# openegg2.net
KiCad netlist of a schematic drawn in EAGLE
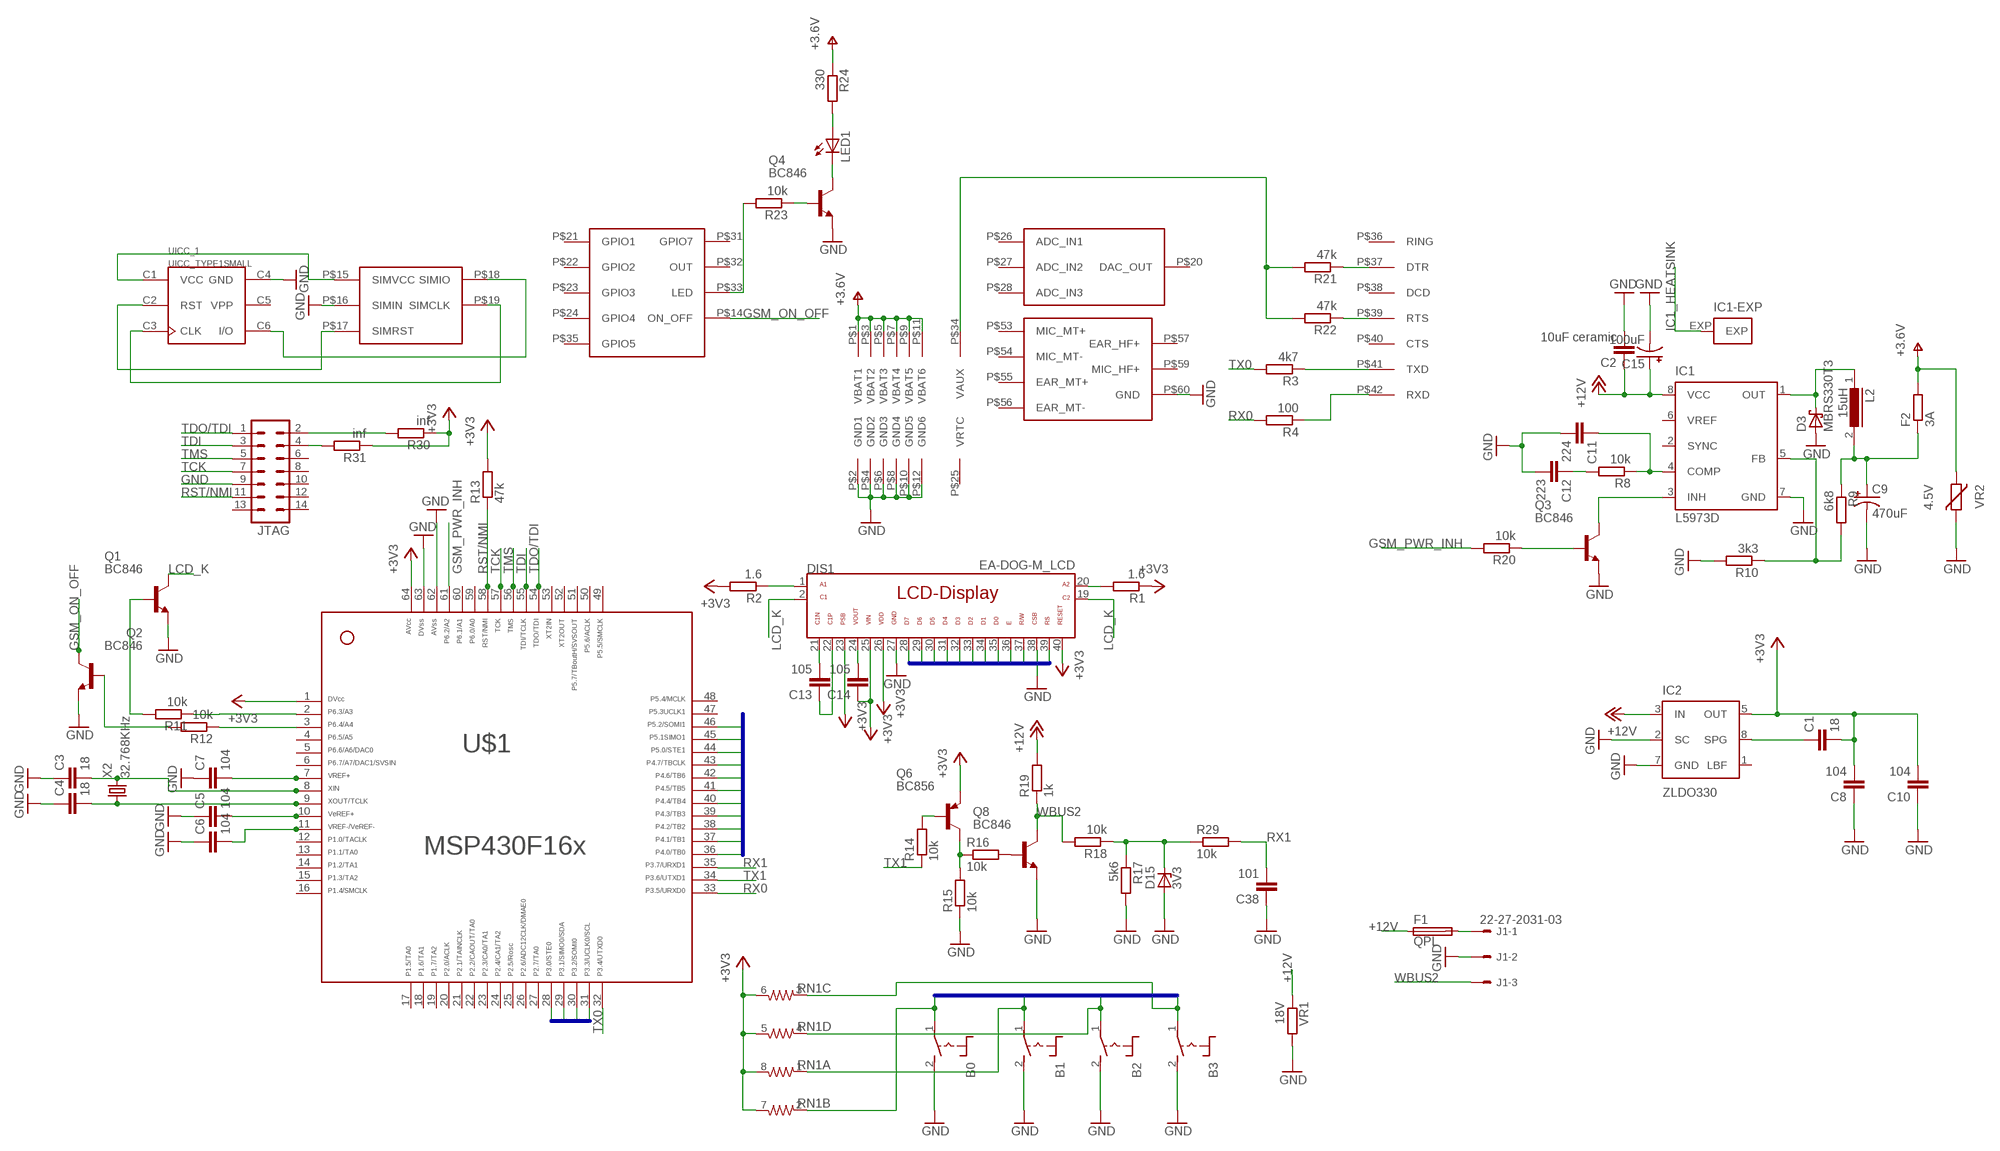
[diagram p0: schematic, sheet 1]

(export (version "E")
  (design (tool "Eeschema 10.0.6"))
  (components
    (comp (ref "B0")
      (value "MARQ6424")
      (footprint "eagle-import:MARQ6424_NOLED")
      (libsource (lib "eagle-import") (part "MARQ6424"))
    )
    (comp (ref "B1")
      (value "MARQ6424")
      (footprint "eagle-import:MARQ6424_NOLED")
      (libsource (lib "eagle-import") (part "MARQ6424"))
    )
    (comp (ref "B2")
      (value "MARQ6424")
      (footprint "eagle-import:MARQ6424_NOLED")
      (libsource (lib "eagle-import") (part "MARQ6424"))
    )
    (comp (ref "B3")
      (value "MARQ6424")
      (footprint "eagle-import:MARQ6424_NOLED")
      (libsource (lib "eagle-import") (part "MARQ6424"))
    )
    (comp (ref "C1")
      (value "18")
      (footprint "eagle-import:C0603")
      (libsource (lib "eagle-import") (part "C-EUC0603"))
    )
    (comp (ref "C2")
      (value "10uF ceramic")
      (footprint "eagle-import:C1210K")
      (libsource (lib "eagle-import") (part "C-EUC1210K"))
    )
    (comp (ref "C3")
      (value "18")
      (footprint "eagle-import:C0603")
      (libsource (lib "eagle-import") (part "C-EUC0603"))
    )
    (comp (ref "C4")
      (value "18")
      (footprint "eagle-import:C0603")
      (libsource (lib "eagle-import") (part "C-EUC0603"))
    )
    (comp (ref "C5")
      (value "104")
      (footprint "eagle-import:C0603")
      (libsource (lib "eagle-import") (part "C-EUC0603"))
    )
    (comp (ref "C6")
      (value "104")
      (footprint "eagle-import:C0603")
      (libsource (lib "eagle-import") (part "C-EUC0603"))
    )
    (comp (ref "C7")
      (value "104")
      (footprint "eagle-import:C0603")
      (libsource (lib "eagle-import") (part "C-EUC0603"))
    )
    (comp (ref "C8")
      (value "104")
      (footprint "eagle-import:C1206")
      (libsource (lib "eagle-import") (part "C-EUC1206"))
    )
    (comp (ref "C9")
      (value "470uF")
      (footprint "eagle-import:CT7343")
      (libsource (lib "eagle-import") (part "CPOL-USCT7343"))
    )
    (comp (ref "C10")
      (value "104")
      (footprint "eagle-import:C1206")
      (libsource (lib "eagle-import") (part "C-EUC1206"))
    )
    (comp (ref "C11")
      (value "224")
      (footprint "eagle-import:C0402")
      (libsource (lib "eagle-import") (part "C-EUC0402"))
    )
    (comp (ref "C12")
      (value "223")
      (footprint "eagle-import:C0402")
      (libsource (lib "eagle-import") (part "C-EUC0402"))
    )
    (comp (ref "C13")
      (value "105")
      (footprint "eagle-import:C1206")
      (libsource (lib "eagle-import") (part "C-EUC1206"))
    )
    (comp (ref "C14")
      (value "105")
      (footprint "eagle-import:C1206")
      (libsource (lib "eagle-import") (part "C-EUC1206"))
    )
    (comp (ref "C15")
      (value "100uF")
      (footprint "eagle-import:153CLV-0505")
      (libsource (lib "eagle-import") (part "CPOL-US153CLV-0505"))
    )
    (comp (ref "C38")
      (value "101")
      (footprint "eagle-import:C0402")
      (libsource (lib "eagle-import") (part "C-EUC0402"))
    )
    (comp (ref "D3")
      (value "MBRS330T3")
      (footprint "eagle-import:SMC")
      (libsource (lib "eagle-import") (part "MBRS30T33"))
    )
    (comp (ref "D15")
      (value "3V3")
      (footprint "eagle-import:SOD80C")
      (libsource (lib "eagle-import") (part "ZENER-DIODESOD80C"))
    )
    (comp (ref "DIS1")
      (value "EA-DOG-M_LCD")
      (footprint "eagle-import:EA-DOG-M_LCD")
      (libsource (lib "eagle-import") (part "EA-DOG-M_LCD"))
    )
    (comp (ref "F1")
      (value "QPL")
      (footprint "eagle-import:QPL")
      (libsource (lib "eagle-import") (part "QPL"))
    )
    (comp (ref "F2")
      (value "3A")
      (footprint "eagle-import:R2010")
      (libsource (lib "eagle-import") (part "R-EU_R2010"))
    )
    (comp (ref "IC1")
      (value "L5973D")
      (footprint "eagle-import:HSOP8")
      (fields (field (name "MF") "STMICROELECTRONICS"))
      (libsource (lib "eagle-import") (part "L5973D"))
    )
    (comp (ref "IC2")
      (value "ZLDO330")
      (footprint "eagle-import:SM8")
      (libsource (lib "eagle-import") (part "ZLDO330"))
    )
    (comp (ref "J1")
      (value "22-27-2031-03")
      (footprint "eagle-import:6410-03")
      (libsource (lib "eagle-import") (part "22-?-0327-2031"))
    )
    (comp (ref "JTAG")
      (value "MA07-2")
      (footprint "eagle-import:MA07-2")
      (libsource (lib "eagle-import") (part "MA07-2"))
    )
    (comp (ref "L2")
      (value "15uH")
      (footprint "eagle-import:DR127")
      (libsource (lib "eagle-import") (part "DR127"))
    )
    (comp (ref "LED1")
      (value "LEDCHIP-LED0603")
      (footprint "eagle-import:CHIP-LED0603")
      (libsource (lib "eagle-import") (part "LEDCHIP-LED0603"))
    )
    (comp (ref "Q1")
      (value "BC846")
      (footprint "eagle-import:SOT23")
      (libsource (lib "eagle-import") (part "BC846SMDALT1"))
    )
    (comp (ref "Q2")
      (value "BC846")
      (footprint "eagle-import:SOT23")
      (libsource (lib "eagle-import") (part "BC846SMDALT1"))
    )
    (comp (ref "Q3")
      (value "BC846")
      (footprint "eagle-import:SOT23")
      (libsource (lib "eagle-import") (part "BC846SMDALT1"))
    )
    (comp (ref "Q4")
      (value "BC846")
      (footprint "eagle-import:SOT23")
      (libsource (lib "eagle-import") (part "BC846SMDALT1"))
    )
    (comp (ref "Q6")
      (value "BC856")
      (footprint "eagle-import:SOT23-BEC")
      (libsource (lib "eagle-import") (part "BC856SMDALT1"))
    )
    (comp (ref "Q8")
      (value "BC846")
      (footprint "eagle-import:SOT23")
      (libsource (lib "eagle-import") (part "BC846SMDALT1"))
    )
    (comp (ref "R1")
      (value "1.6")
      (footprint "eagle-import:R1206")
      (libsource (lib "eagle-import") (part "R-EU_R1206"))
    )
    (comp (ref "R2")
      (value "1.6")
      (footprint "eagle-import:R1206")
      (libsource (lib "eagle-import") (part "R-EU_R1206"))
    )
    (comp (ref "R3")
      (value "4k7")
      (footprint "eagle-import:R0603")
      (libsource (lib "eagle-import") (part "R-EU_R0603"))
    )
    (comp (ref "R4")
      (value "100")
      (footprint "eagle-import:R0603")
      (libsource (lib "eagle-import") (part "R-EU_R0603"))
    )
    (comp (ref "R8")
      (value "10k")
      (footprint "eagle-import:R0603")
      (libsource (lib "eagle-import") (part "R-EU_R0603"))
    )
    (comp (ref "R9")
      (value "6k8")
      (footprint "eagle-import:R0603")
      (libsource (lib "eagle-import") (part "R-EU_R0603"))
    )
    (comp (ref "R10")
      (value "3k3")
      (footprint "eagle-import:R0603")
      (libsource (lib "eagle-import") (part "R-EU_R0603"))
    )
    (comp (ref "R11")
      (value "10k")
      (footprint "eagle-import:R0603")
      (libsource (lib "eagle-import") (part "R-EU_R0603"))
    )
    (comp (ref "R12")
      (value "10k")
      (footprint "eagle-import:R0603")
      (libsource (lib "eagle-import") (part "R-EU_R0603"))
    )
    (comp (ref "R13")
      (value "47k")
      (footprint "eagle-import:R0603")
      (libsource (lib "eagle-import") (part "R-EU_R0603"))
    )
    (comp (ref "R14")
      (value "10k")
      (footprint "eagle-import:R0603")
      (libsource (lib "eagle-import") (part "R-EU_R0603"))
    )
    (comp (ref "R15")
      (value "10k")
      (footprint "eagle-import:R0603")
      (libsource (lib "eagle-import") (part "R-EU_R0603"))
    )
    (comp (ref "R16")
      (value "10k")
      (footprint "eagle-import:R0603")
      (libsource (lib "eagle-import") (part "R-EU_R0603"))
    )
    (comp (ref "R17")
      (value "5k6")
      (footprint "eagle-import:R0603")
      (libsource (lib "eagle-import") (part "R-EU_R0603"))
    )
    (comp (ref "R18")
      (value "10k")
      (footprint "eagle-import:R0603")
      (libsource (lib "eagle-import") (part "R-EU_R0603"))
    )
    (comp (ref "R19")
      (value "1k")
      (footprint "eagle-import:R0603")
      (libsource (lib "eagle-import") (part "R-EU_R0603"))
    )
    (comp (ref "R20")
      (value "10k")
      (footprint "eagle-import:R0603")
      (libsource (lib "eagle-import") (part "R-EU_R0603"))
    )
    (comp (ref "R21")
      (value "47k")
      (footprint "eagle-import:R0603")
      (libsource (lib "eagle-import") (part "R-EU_R0603"))
    )
    (comp (ref "R22")
      (value "47k")
      (footprint "eagle-import:R0603")
      (libsource (lib "eagle-import") (part "R-EU_R0603"))
    )
    (comp (ref "R23")
      (value "10k")
      (footprint "eagle-import:R0603")
      (libsource (lib "eagle-import") (part "R-EU_R0603"))
    )
    (comp (ref "R24")
      (value "330")
      (footprint "eagle-import:R0603")
      (libsource (lib "eagle-import") (part "R-EU_R0603"))
    )
    (comp (ref "R29")
      (value "10k")
      (footprint "eagle-import:R0603")
      (libsource (lib "eagle-import") (part "R-EU_R0603"))
    )
    (comp (ref "R30")
      (value "inf")
      (footprint "eagle-import:R0603")
      (libsource (lib "eagle-import") (part "R-EU_R0603"))
    )
    (comp (ref "R31")
      (value "inf")
      (footprint "eagle-import:R0603")
      (libsource (lib "eagle-import") (part "R-EU_R0603"))
    )
    (comp (ref "RN1")
      (value "742-8_S")
      (footprint "eagle-import:742-8")
      (libsource (lib "eagle-import") (part "742-8_S"))
    )
    (comp (ref "U$1")
      (value "F16X---PM64")
      (footprint "eagle-import:PM_PAG64")
      (libsource (lib "eagle-import") (part "F16X---PM64"))
    )
    (comp (ref "U$2")
      (value "GC864-QUAD-C2SMD")
      (footprint "eagle-import:GC864-QUAD-C2_SMD")
      (libsource (lib "eagle-import") (part "GC864-QUAD-C2SMD"))
    )
    (comp (ref "UICC_1")
      (value "UICC_TYPE1SMALL")
      (footprint "eagle-import:UICC_READER2")
      (libsource (lib "eagle-import") (part "UICC_TYPE1SMALL"))
    )
    (comp (ref "VR1")
      (value "18V")
      (footprint "eagle-import:R2010")
      (libsource (lib "eagle-import") (part "R-EU_R2010"))
    )
    (comp (ref "VR2")
      (value "4.5V")
      (footprint "eagle-import:CT_CN1812")
      (libsource (lib "eagle-import") (part "VARISTORCN1812"))
    )
    (comp (ref "X2")
      (value "32.768KHz")
      (footprint "eagle-import:TC26V")
      (libsource (lib "eagle-import") (part "CRYSTALTC26V"))
    )
  )
  (nets
    (net (code "1") (name "+3.6V") (class "Default")
      (node (ref "F2") (pin "2") (pinfunction "2_2") (pintype "passive"))
      (node (ref "R24") (pin "1") (pinfunction "1_1") (pintype "passive"))
      (node (ref "U$2") (pin "P$1") (pinfunction "VBAT1_P$1") (pintype "power_in"))
      (node (ref "U$2") (pin "P$11") (pinfunction "VBAT6_P$11") (pintype "power_in"))
      (node (ref "U$2") (pin "P$3") (pinfunction "VBAT2_P$3") (pintype "power_in"))
      (node (ref "U$2") (pin "P$5") (pinfunction "VBAT3_P$5") (pintype "power_in"))
      (node (ref "U$2") (pin "P$7") (pinfunction "VBAT4_P$7") (pintype "power_in"))
      (node (ref "U$2") (pin "P$9") (pinfunction "VBAT5_P$9") (pintype "power_in"))
      (node (ref "VR2") (pin "2") (pinfunction "2_2") (pintype "passive"))
    )
    (net (code "2") (name "+3V3") (class "Default")
      (node (ref "C1") (pin "2") (pinfunction "2_2") (pintype "passive"))
      (node (ref "C10") (pin "2") (pinfunction "2_2") (pintype "passive"))
      (node (ref "C14") (pin "1") (pinfunction "1_1") (pintype "passive"))
      (node (ref "C8") (pin "2") (pinfunction "2_2") (pintype "passive"))
      (node (ref "DIS1") (pin "23") (pinfunction "23_23") (pintype "bidirectional"))
      (node (ref "DIS1") (pin "25") (pinfunction "25_25") (pintype "bidirectional"))
      (node (ref "DIS1") (pin "26") (pinfunction "26_26") (pintype "power_in"))
      (node (ref "DIS1") (pin "40") (pinfunction "40_40") (pintype "bidirectional"))
      (node (ref "IC2") (pin "5") (pinfunction "OUT_5") (pintype "power_in"))
      (node (ref "Q6") (pin "E") (pinfunction "E_E") (pintype "passive"))
      (node (ref "R1") (pin "1") (pinfunction "1_1") (pintype "passive"))
      (node (ref "R13") (pin "2") (pinfunction "2_2") (pintype "passive"))
      (node (ref "R2") (pin "2") (pinfunction "2_2") (pintype "passive"))
      (node (ref "R30") (pin "1") (pinfunction "1_1") (pintype "passive"))
      (node (ref "R31") (pin "1") (pinfunction "1_1") (pintype "passive"))
      (node (ref "RN1") (pin "5") (pinfunction "2_5") (pintype "passive"))
      (node (ref "RN1") (pin "6") (pinfunction "2_6") (pintype "passive"))
      (node (ref "RN1") (pin "7") (pinfunction "2_7") (pintype "passive"))
      (node (ref "RN1") (pin "8") (pinfunction "2_8") (pintype "passive"))
      (node (ref "U$1") (pin "1") (pinfunction "1_1") (pintype "power_in"))
      (node (ref "U$1") (pin "64") (pinfunction "64_64") (pintype "power_in"))
    )
    (net (code "3") (name "+12V") (class "Default")
      (node (ref "C15") (pin "+") (pinfunction "+_+") (pintype "passive"))
      (node (ref "C2") (pin "1") (pinfunction "1_1") (pintype "passive"))
      (node (ref "F1") (pin "1") (pinfunction "1_1") (pintype "passive"))
      (node (ref "IC1") (pin "8") (pinfunction "VCC_8") (pintype "input"))
      (node (ref "IC2") (pin "3") (pinfunction "IN_3") (pintype "input"))
      (node (ref "R19") (pin "2") (pinfunction "2_2") (pintype "passive"))
      (node (ref "VR1") (pin "1") (pinfunction "1_1") (pintype "passive"))
    )
    (net (code "4") (name "/B0") (class "Default")
      (node (ref "B0") (pin "1") (pinfunction "P_1") (pintype "passive"))
      (node (ref "RN1") (pin "2") (pinfunction "1_2") (pintype "passive"))
      (node (ref "U$1") (pin "30") (pinfunction "30_30") (pintype "bidirectional"))
    )
    (net (code "5") (name "/B1") (class "Default")
      (node (ref "B1") (pin "1") (pinfunction "P_1") (pintype "passive"))
      (node (ref "RN1") (pin "1") (pinfunction "1_1") (pintype "passive"))
      (node (ref "U$1") (pin "31") (pinfunction "31_31") (pintype "bidirectional"))
    )
    (net (code "6") (name "/B2") (class "Default")
      (node (ref "B2") (pin "1") (pinfunction "P_1") (pintype "passive"))
      (node (ref "RN1") (pin "4") (pinfunction "1_4") (pintype "passive"))
      (node (ref "U$1") (pin "28") (pinfunction "28_28") (pintype "bidirectional"))
    )
    (net (code "7") (name "/B3") (class "Default")
      (node (ref "B3") (pin "1") (pinfunction "P_1") (pintype "passive"))
      (node (ref "RN1") (pin "3") (pinfunction "1_3") (pintype "passive"))
      (node (ref "U$1") (pin "29") (pinfunction "29_29") (pintype "bidirectional"))
    )
    (net (code "8") (name "/D0") (class "Default")
      (node (ref "DIS1") (pin "35") (pinfunction "35_35") (pintype "bidirectional"))
      (node (ref "U$1") (pin "36") (pinfunction "36_36") (pintype "output"))
    )
    (net (code "9") (name "/D1") (class "Default")
      (node (ref "DIS1") (pin "34") (pinfunction "34_34") (pintype "bidirectional"))
      (node (ref "U$1") (pin "37") (pinfunction "37_37") (pintype "bidirectional"))
    )
    (net (code "10") (name "/D2") (class "Default")
      (node (ref "DIS1") (pin "33") (pinfunction "33_33") (pintype "bidirectional"))
      (node (ref "U$1") (pin "38") (pinfunction "38_38") (pintype "bidirectional"))
    )
    (net (code "11") (name "/D3") (class "Default")
      (node (ref "DIS1") (pin "32") (pinfunction "32_32") (pintype "bidirectional"))
      (node (ref "U$1") (pin "39") (pinfunction "39_39") (pintype "bidirectional"))
    )
    (net (code "12") (name "/D4") (class "Default")
      (node (ref "DIS1") (pin "31") (pinfunction "31_31") (pintype "bidirectional"))
      (node (ref "U$1") (pin "40") (pinfunction "40_40") (pintype "input"))
    )
    (net (code "13") (name "/D5") (class "Default")
      (node (ref "DIS1") (pin "30") (pinfunction "30_30") (pintype "bidirectional"))
      (node (ref "U$1") (pin "41") (pinfunction "41_41") (pintype "bidirectional"))
    )
    (net (code "14") (name "/D6") (class "Default")
      (node (ref "DIS1") (pin "29") (pinfunction "29_29") (pintype "bidirectional"))
      (node (ref "U$1") (pin "42") (pinfunction "42_42") (pintype "bidirectional"))
    )
    (net (code "15") (name "/D7") (class "Default")
      (node (ref "DIS1") (pin "28") (pinfunction "28_28") (pintype "bidirectional"))
      (node (ref "U$1") (pin "43") (pinfunction "43_43") (pintype "bidirectional"))
    )
    (net (code "16") (name "/E") (class "Default")
      (node (ref "DIS1") (pin "36") (pinfunction "36_36") (pintype "bidirectional"))
      (node (ref "U$1") (pin "45") (pinfunction "45_45") (pintype "bidirectional"))
    )
    (net (code "17") (name "/GSM_ON_OFF") (class "Default")
      (node (ref "Q2") (pin "3") (pinfunction "C_3") (pintype "passive"))
      (node (ref "U$2") (pin "P$14") (pinfunction "ON_OFF_P$14") (pintype "input"))
    )
    (net (code "18") (name "/GSM_PWR_INH") (class "Default")
      (node (ref "R20") (pin "2") (pinfunction "2_2") (pintype "passive"))
      (node (ref "U$1") (pin "61") (pinfunction "61_61") (pintype "bidirectional"))
    )
    (net (code "19") (name "/IC1_HEATSINK") (class "Default")
      (node (ref "IC1") (pin "EXP") (pinfunction "EXP_EXP") (pintype "input"))
    )
    (net (code "20") (name "/LCD_K") (class "Default")
      (node (ref "DIS1") (pin "19") (pinfunction "19_19") (pintype "passive"))
      (node (ref "DIS1") (pin "2") (pinfunction "2_2") (pintype "passive"))
      (node (ref "Q1") (pin "3") (pinfunction "C_3") (pintype "passive"))
    )
    (net (code "21") (name "/RS") (class "Default")
      (node (ref "DIS1") (pin "39") (pinfunction "39_39") (pintype "bidirectional"))
      (node (ref "U$1") (pin "46") (pinfunction "46_46") (pintype "bidirectional"))
    )
    (net (code "22") (name "/RST{slash}NMI") (class "Default")
      (node (ref "JTAG") (pin "11") (pinfunction "11_11") (pintype "passive"))
      (node (ref "R13") (pin "1") (pinfunction "1_1") (pintype "passive"))
      (node (ref "U$1") (pin "58") (pinfunction "58_58") (pintype "input"))
    )
    (net (code "23") (name "/RW") (class "Default")
      (node (ref "DIS1") (pin "37") (pinfunction "37_37") (pintype "bidirectional"))
      (node (ref "U$1") (pin "44") (pinfunction "44_44") (pintype "bidirectional"))
    )
    (net (code "24") (name "/RX0") (class "Default")
      (node (ref "R4") (pin "2") (pinfunction "2_2") (pintype "passive"))
      (node (ref "U$1") (pin "33") (pinfunction "33_33") (pintype "bidirectional"))
    )
    (net (code "25") (name "/RX1") (class "Default")
      (node (ref "C38") (pin "2") (pinfunction "2_2") (pintype "passive"))
      (node (ref "R29") (pin "2") (pinfunction "2_2") (pintype "passive"))
      (node (ref "U$1") (pin "35") (pinfunction "35_35") (pintype "bidirectional"))
    )
    (net (code "26") (name "/TCK") (class "Default")
      (node (ref "JTAG") (pin "7") (pinfunction "7_7") (pintype "passive"))
      (node (ref "U$1") (pin "57") (pinfunction "57_57") (pintype "input"))
    )
    (net (code "27") (name "/TDI") (class "Default")
      (node (ref "JTAG") (pin "3") (pinfunction "3_3") (pintype "passive"))
      (node (ref "U$1") (pin "55") (pinfunction "55_55") (pintype "input"))
    )
    (net (code "28") (name "/TDO{slash}TDI") (class "Default")
      (node (ref "JTAG") (pin "1") (pinfunction "1_1") (pintype "passive"))
      (node (ref "U$1") (pin "54") (pinfunction "54_54") (pintype "bidirectional"))
    )
    (net (code "29") (name "/TMS") (class "Default")
      (node (ref "JTAG") (pin "5") (pinfunction "5_5") (pintype "passive"))
      (node (ref "U$1") (pin "56") (pinfunction "56_56") (pintype "input"))
    )
    (net (code "30") (name "/TX0") (class "Default")
      (node (ref "R3") (pin "2") (pinfunction "2_2") (pintype "passive"))
      (node (ref "U$1") (pin "32") (pinfunction "32_32") (pintype "bidirectional"))
    )
    (net (code "31") (name "/TX1") (class "Default")
      (node (ref "R14") (pin "1") (pinfunction "1_1") (pintype "passive"))
      (node (ref "U$1") (pin "34") (pinfunction "34_34") (pintype "bidirectional"))
    )
    (net (code "32") (name "/VPP") (class "Default")
      (node (ref "UICC_1") (pin "C5") (pinfunction "VPP_C5") (pintype "power_in"))
    )
    (net (code "33") (name "/WBUS2") (class "Default")
      (node (ref "J1") (pin "3") (pinfunction "S_3") (pintype "passive"))
      (node (ref "Q8") (pin "3") (pinfunction "C_3") (pintype "passive"))
      (node (ref "R18") (pin "2") (pinfunction "2_2") (pintype "passive"))
      (node (ref "R19") (pin "1") (pinfunction "1_1") (pintype "passive"))
    )
    (net (code "34") (name "GND") (class "Default")
      (node (ref "B0") (pin "2") (pinfunction "S_2") (pintype "passive"))
      (node (ref "B1") (pin "2") (pinfunction "S_2") (pintype "passive"))
      (node (ref "B2") (pin "2") (pinfunction "S_2") (pintype "passive"))
      (node (ref "B3") (pin "2") (pinfunction "S_2") (pintype "passive"))
      (node (ref "C10") (pin "1") (pinfunction "1_1") (pintype "passive"))
      (node (ref "C11") (pin "2") (pinfunction "2_2") (pintype "passive"))
      (node (ref "C12") (pin "2") (pinfunction "2_2") (pintype "passive"))
      (node (ref "C15") (pin "-") (pinfunction "-_-") (pintype "passive"))
      (node (ref "C2") (pin "2") (pinfunction "2_2") (pintype "passive"))
      (node (ref "C3") (pin "1") (pinfunction "1_1") (pintype "passive"))
      (node (ref "C38") (pin "1") (pinfunction "1_1") (pintype "passive"))
      (node (ref "C4") (pin "1") (pinfunction "1_1") (pintype "passive"))
      (node (ref "C5") (pin "1") (pinfunction "1_1") (pintype "passive"))
      (node (ref "C6") (pin "1") (pinfunction "1_1") (pintype "passive"))
      (node (ref "C7") (pin "1") (pinfunction "1_1") (pintype "passive"))
      (node (ref "C8") (pin "1") (pinfunction "1_1") (pintype "passive"))
      (node (ref "C9") (pin "-") (pinfunction "-_-") (pintype "passive"))
      (node (ref "D15") (pin "A") (pinfunction "A_A") (pintype "passive"))
      (node (ref "D3") (pin "A") (pinfunction "A_A") (pintype "passive"))
      (node (ref "DIS1") (pin "27") (pinfunction "27_27") (pintype "power_in"))
      (node (ref "DIS1") (pin "38") (pinfunction "38_38") (pintype "bidirectional"))
      (node (ref "IC1") (pin "7") (pinfunction "GND_7") (pintype "power_in"))
      (node (ref "IC2") (pin "2") (pinfunction "SC_2") (pintype "input"))
      (node (ref "IC2") (pin "7") (pinfunction "GND_7") (pintype "power_in"))
      (node (ref "J1") (pin "2") (pinfunction "S_2") (pintype "passive"))
      (node (ref "JTAG") (pin "9") (pinfunction "9_9") (pintype "passive"))
      (node (ref "Q1") (pin "2") (pinfunction "E_2") (pintype "passive"))
      (node (ref "Q2") (pin "2") (pinfunction "E_2") (pintype "passive"))
      (node (ref "Q3") (pin "2") (pinfunction "E_2") (pintype "passive"))
      (node (ref "Q4") (pin "2") (pinfunction "E_2") (pintype "passive"))
      (node (ref "Q8") (pin "2") (pinfunction "E_2") (pintype "passive"))
      (node (ref "R10") (pin "2") (pinfunction "2_2") (pintype "passive"))
      (node (ref "R15") (pin "1") (pinfunction "1_1") (pintype "passive"))
      (node (ref "R17") (pin "2") (pinfunction "2_2") (pintype "passive"))
      (node (ref "U$1") (pin "62") (pinfunction "62_62") (pintype "power_in"))
      (node (ref "U$1") (pin "63") (pinfunction "63_63") (pintype "power_in"))
      (node (ref "U$2") (pin "P$10") (pinfunction "GND5_P$10") (pintype "power_in"))
      (node (ref "U$2") (pin "P$12") (pinfunction "GND6_P$12") (pintype "power_in"))
      (node (ref "U$2") (pin "P$16") (pinfunction "SIMIN_P$16") (pintype "input"))
      (node (ref "U$2") (pin "P$2") (pinfunction "GND1_P$2") (pintype "power_in"))
      (node (ref "U$2") (pin "P$4") (pinfunction "GND2_P$4") (pintype "power_in"))
      (node (ref "U$2") (pin "P$6") (pinfunction "GND3_P$6") (pintype "power_in"))
      (node (ref "U$2") (pin "P$60") (pinfunction "GND_P$60") (pintype "power_in"))
      (node (ref "U$2") (pin "P$8") (pinfunction "GND4_P$8") (pintype "power_in"))
      (node (ref "UICC_1") (pin "C4") (pinfunction "GND_C4") (pintype "power_in"))
      (node (ref "VR1") (pin "2") (pinfunction "2_2") (pintype "passive"))
      (node (ref "VR2") (pin "1") (pinfunction "1_1") (pintype "passive"))
    )
    (net (code "35") (name "Net-(C3-Pad2)") (class "Default")
      (node (ref "C3") (pin "2") (pinfunction "2_2") (pintype "passive"))
      (node (ref "U$1") (pin "8") (pinfunction "8_8") (pintype "input"))
      (node (ref "X2") (pin "2") (pinfunction "2_2") (pintype "passive"))
    )
    (net (code "36") (name "Net-(C4-Pad2)") (class "Default")
      (node (ref "C4") (pin "2") (pinfunction "2_2") (pintype "passive"))
      (node (ref "U$1") (pin "9") (pinfunction "9_9") (pintype "bidirectional"))
      (node (ref "X2") (pin "1") (pinfunction "1_1") (pintype "passive"))
    )
    (net (code "37") (name "Net-(C5-Pad2)") (class "Default")
      (node (ref "C5") (pin "2") (pinfunction "2_2") (pintype "passive"))
      (node (ref "U$1") (pin "10") (pinfunction "10_10") (pintype "input"))
    )
    (net (code "38") (name "Net-(C6-Pad2)") (class "Default")
      (node (ref "C6") (pin "2") (pinfunction "2_2") (pintype "passive"))
      (node (ref "U$1") (pin "11") (pinfunction "11_11") (pintype "bidirectional"))
    )
    (net (code "39") (name "Net-(C7-Pad2)") (class "Default")
      (node (ref "C7") (pin "2") (pinfunction "2_2") (pintype "passive"))
      (node (ref "U$1") (pin "7") (pinfunction "7_7") (pintype "output"))
    )
    (net (code "40") (name "Net-(C9-Pad+)") (class "Default")
      (node (ref "C9") (pin "+") (pinfunction "+_+") (pintype "passive"))
      (node (ref "F2") (pin "1") (pinfunction "1_1") (pintype "passive"))
      (node (ref "L2") (pin "2") (pinfunction "2_2") (pintype "passive"))
      (node (ref "R9") (pin "1") (pinfunction "1_1") (pintype "passive"))
    )
    (net (code "41") (name "Net-(C12-Pad1)") (class "Default")
      (node (ref "C12") (pin "1") (pinfunction "1_1") (pintype "passive"))
      (node (ref "R8") (pin "2") (pinfunction "2_2") (pintype "passive"))
    )
    (net (code "42") (name "Net-(C13-Pad1)") (class "Default")
      (node (ref "C13") (pin "1") (pinfunction "1_1") (pintype "passive"))
      (node (ref "DIS1") (pin "22") (pinfunction "22_22") (pintype "bidirectional"))
    )
    (net (code "43") (name "Net-(C13-Pad2)") (class "Default")
      (node (ref "C13") (pin "2") (pinfunction "2_2") (pintype "passive"))
      (node (ref "DIS1") (pin "21") (pinfunction "21_21") (pintype "bidirectional"))
    )
    (net (code "44") (name "Net-(C14-Pad2)") (class "Default")
      (node (ref "C14") (pin "2") (pinfunction "2_2") (pintype "passive"))
      (node (ref "DIS1") (pin "24") (pinfunction "24_24") (pintype "bidirectional"))
    )
    (net (code "45") (name "Net-(D15-PadC)") (class "Default")
      (node (ref "D15") (pin "C") (pinfunction "C_C") (pintype "passive"))
      (node (ref "R17") (pin "1") (pinfunction "1_1") (pintype "passive"))
      (node (ref "R18") (pin "1") (pinfunction "1_1") (pintype "passive"))
      (node (ref "R29") (pin "1") (pinfunction "1_1") (pintype "passive"))
    )
    (net (code "46") (name "Net-(DIS1-Pad1)") (class "Default")
      (node (ref "DIS1") (pin "1") (pinfunction "1_1") (pintype "passive"))
      (node (ref "R2") (pin "1") (pinfunction "1_1") (pintype "passive"))
    )
    (net (code "47") (name "Net-(DIS1-Pad20)") (class "Default")
      (node (ref "DIS1") (pin "20") (pinfunction "20_20") (pintype "passive"))
      (node (ref "R1") (pin "2") (pinfunction "2_2") (pintype "passive"))
    )
    (net (code "48") (name "Net-(IC1B-COMP)") (class "Default")
      (node (ref "C11") (pin "1") (pinfunction "1_1") (pintype "passive"))
      (node (ref "IC1") (pin "4") (pinfunction "COMP_4") (pintype "passive"))
      (node (ref "R8") (pin "1") (pinfunction "1_1") (pintype "passive"))
    )
    (net (code "49") (name "Net-(IC1B-FB)") (class "Default")
      (node (ref "IC1") (pin "5") (pinfunction "FB_5") (pintype "input"))
      (node (ref "R10") (pin "1") (pinfunction "1_1") (pintype "passive"))
      (node (ref "R9") (pin "2") (pinfunction "2_2") (pintype "passive"))
    )
    (net (code "50") (name "Net-(IC1B-INH)") (class "Default")
      (node (ref "IC1") (pin "3") (pinfunction "INH_3") (pintype "input"))
      (node (ref "Q3") (pin "3") (pinfunction "C_3") (pintype "passive"))
    )
    (net (code "51") (name "Net-(IC1B-OUT)") (class "Default")
      (node (ref "D3") (pin "C") (pinfunction "C_C") (pintype "passive"))
      (node (ref "IC1") (pin "1") (pinfunction "OUT_1") (pintype "output"))
      (node (ref "L2") (pin "1") (pinfunction "1_1") (pintype "passive"))
    )
    (net (code "52") (name "Net-(IC2-SPG)") (class "Default")
      (node (ref "C1") (pin "1") (pinfunction "1_1") (pintype "passive"))
      (node (ref "IC2") (pin "8") (pinfunction "SPG_8") (pintype "input"))
    )
    (net (code "53") (name "Net-(J1A-S)") (class "Default")
      (node (ref "F1") (pin "2") (pinfunction "2_2") (pintype "passive"))
      (node (ref "J1") (pin "1") (pinfunction "S_1") (pintype "passive"))
    )
    (net (code "54") (name "Net-(JTAG-Pad2)") (class "Default")
      (node (ref "JTAG") (pin "2") (pinfunction "2_2") (pintype "passive"))
      (node (ref "R30") (pin "2") (pinfunction "2_2") (pintype "passive"))
    )
    (net (code "55") (name "Net-(JTAG-Pad4)") (class "Default")
      (node (ref "JTAG") (pin "4") (pinfunction "4_4") (pintype "passive"))
      (node (ref "R31") (pin "2") (pinfunction "2_2") (pintype "passive"))
    )
    (net (code "56") (name "Net-(LED1-PadA)") (class "Default")
      (node (ref "LED1") (pin "A") (pinfunction "A_A") (pintype "passive"))
      (node (ref "R24") (pin "2") (pinfunction "2_2") (pintype "passive"))
    )
    (net (code "57") (name "Net-(Q1-B)") (class "Default")
      (node (ref "Q1") (pin "1") (pinfunction "B_1") (pintype "passive"))
      (node (ref "R11") (pin "2") (pinfunction "2_2") (pintype "passive"))
    )
    (net (code "58") (name "Net-(Q2-B)") (class "Default")
      (node (ref "Q2") (pin "1") (pinfunction "B_1") (pintype "passive"))
      (node (ref "R12") (pin "2") (pinfunction "2_2") (pintype "passive"))
    )
    (net (code "59") (name "Net-(Q3-B)") (class "Default")
      (node (ref "Q3") (pin "1") (pinfunction "B_1") (pintype "passive"))
      (node (ref "R20") (pin "1") (pinfunction "1_1") (pintype "passive"))
    )
    (net (code "60") (name "Net-(Q4-B)") (class "Default")
      (node (ref "Q4") (pin "1") (pinfunction "B_1") (pintype "passive"))
      (node (ref "R23") (pin "1") (pinfunction "1_1") (pintype "passive"))
    )
    (net (code "61") (name "Net-(Q4-C)") (class "Default")
      (node (ref "LED1") (pin "C") (pinfunction "C_C") (pintype "passive"))
      (node (ref "Q4") (pin "3") (pinfunction "C_3") (pintype "passive"))
    )
    (net (code "62") (name "Net-(Q6-PadB)") (class "Default")
      (node (ref "Q6") (pin "B") (pinfunction "B_B") (pintype "passive"))
      (node (ref "R14") (pin "2") (pinfunction "2_2") (pintype "passive"))
    )
    (net (code "63") (name "Net-(Q6-PadC)") (class "Default")
      (node (ref "Q6") (pin "C") (pinfunction "C_C") (pintype "passive"))
      (node (ref "R15") (pin "2") (pinfunction "2_2") (pintype "passive"))
      (node (ref "R16") (pin "1") (pinfunction "1_1") (pintype "passive"))
    )
    (net (code "64") (name "Net-(Q8-B)") (class "Default")
      (node (ref "Q8") (pin "1") (pinfunction "B_1") (pintype "passive"))
      (node (ref "R16") (pin "2") (pinfunction "2_2") (pintype "passive"))
    )
    (net (code "65") (name "Net-(R11-Pad1)") (class "Default")
      (node (ref "R11") (pin "1") (pinfunction "1_1") (pintype "passive"))
      (node (ref "U$1") (pin "2") (pinfunction "2_2") (pintype "bidirectional"))
    )
    (net (code "66") (name "Net-(R12-Pad1)") (class "Default")
      (node (ref "R12") (pin "1") (pinfunction "1_1") (pintype "passive"))
      (node (ref "U$1") (pin "3") (pinfunction "3_3") (pintype "bidirectional"))
    )
    (net (code "67") (name "Net-(U$2A-VAUX)") (class "Default")
      (node (ref "R21") (pin "2") (pinfunction "2_2") (pintype "passive"))
      (node (ref "R22") (pin "2") (pinfunction "2_2") (pintype "passive"))
      (node (ref "U$2") (pin "P$34") (pinfunction "VAUX_P$34") (pintype "power_in"))
    )
    (net (code "68") (name "Net-(U$2D-LED)") (class "Default")
      (node (ref "R23") (pin "2") (pinfunction "2_2") (pintype "passive"))
      (node (ref "U$2") (pin "P$33") (pinfunction "LED_P$33") (pintype "output"))
    )
    (net (code "69") (name "Net-(U$2E-SIMCLK)") (class "Default")
      (node (ref "U$2") (pin "P$19") (pinfunction "SIMCLK_P$19") (pintype "output"))
      (node (ref "UICC_1") (pin "C3") (pinfunction "CLK_C3") (pintype "input"))
    )
    (net (code "70") (name "Net-(U$2E-SIMIO)") (class "Default")
      (node (ref "U$2") (pin "P$18") (pinfunction "SIMIO_P$18") (pintype "bidirectional"))
      (node (ref "UICC_1") (pin "C6") (pinfunction "I/O_C6") (pintype "bidirectional"))
    )
    (net (code "71") (name "Net-(U$2E-SIMRST)") (class "Default")
      (node (ref "U$2") (pin "P$17") (pinfunction "SIMRST_P$17") (pintype "output"))
      (node (ref "UICC_1") (pin "C2") (pinfunction "RST_C2") (pintype "input"))
    )
    (net (code "72") (name "Net-(U$2E-SIMVCC)") (class "Default")
      (node (ref "U$2") (pin "P$15") (pinfunction "SIMVCC_P$15") (pintype "power_in"))
      (node (ref "UICC_1") (pin "C1") (pinfunction "VCC_C1") (pintype "power_in"))
    )
    (net (code "73") (name "Net-(U$2F-DTR)") (class "Default")
      (node (ref "R21") (pin "1") (pinfunction "1_1") (pintype "passive"))
      (node (ref "U$2") (pin "P$37") (pinfunction "DTR_P$37") (pintype "input"))
    )
    (net (code "74") (name "Net-(U$2F-RTS)") (class "Default")
      (node (ref "R22") (pin "1") (pinfunction "1_1") (pintype "passive"))
      (node (ref "U$2") (pin "P$39") (pinfunction "RTS_P$39") (pintype "input"))
    )
    (net (code "75") (name "Net-(U$2F-RXD)") (class "Default")
      (node (ref "R4") (pin "1") (pinfunction "1_1") (pintype "passive"))
      (node (ref "U$2") (pin "P$42") (pinfunction "RXD_P$42") (pintype "output"))
    )
    (net (code "76") (name "Net-(U$2F-TXD)") (class "Default")
      (node (ref "R3") (pin "1") (pinfunction "1_1") (pintype "passive"))
      (node (ref "U$2") (pin "P$41") (pinfunction "TXD_P$41") (pintype "input"))
    )
    (net (code "77") (name "unconnected-(IC1B-SYNC-Pad2)") (class "Default")
      (node (ref "IC1") (pin "2") (pinfunction "SYNC_2") (pintype "input"))
    )
    (net (code "78") (name "unconnected-(IC1B-VREF-Pad6)") (class "Default")
      (node (ref "IC1") (pin "6") (pinfunction "VREF_6") (pintype "input"))
    )
    (net (code "79") (name "unconnected-(IC2-LBF-Pad1)") (class "Default")
      (node (ref "IC2") (pin "1") (pinfunction "LBF_1") (pintype "output"))
    )
    (net (code "80") (name "unconnected-(JTAG-Pad6)") (class "Default")
      (node (ref "JTAG") (pin "6") (pinfunction "6_6") (pintype "passive"))
    )
    (net (code "81") (name "unconnected-(JTAG-Pad8)") (class "Default")
      (node (ref "JTAG") (pin "8") (pinfunction "8_8") (pintype "passive"))
    )
    (net (code "82") (name "unconnected-(JTAG-Pad10)") (class "Default")
      (node (ref "JTAG") (pin "10") (pinfunction "10_10") (pintype "passive"))
    )
    (net (code "83") (name "unconnected-(JTAG-Pad12)") (class "Default")
      (node (ref "JTAG") (pin "12") (pinfunction "12_12") (pintype "passive"))
    )
    (net (code "84") (name "unconnected-(JTAG-Pad13)") (class "Default")
      (node (ref "JTAG") (pin "13") (pinfunction "13_13") (pintype "passive"))
    )
    (net (code "85") (name "unconnected-(JTAG-Pad14)") (class "Default")
      (node (ref "JTAG") (pin "14") (pinfunction "14_14") (pintype "passive"))
    )
    (net (code "86") (name "unconnected-(U$1-Pad4)") (class "Default")
      (node (ref "U$1") (pin "4") (pinfunction "4_4") (pintype "bidirectional"))
    )
    (net (code "87") (name "unconnected-(U$1-Pad5)") (class "Default")
      (node (ref "U$1") (pin "5") (pinfunction "5_5") (pintype "bidirectional"))
    )
    (net (code "88") (name "unconnected-(U$1-Pad6)") (class "Default")
      (node (ref "U$1") (pin "6") (pinfunction "6_6") (pintype "bidirectional"))
    )
    (net (code "89") (name "unconnected-(U$1-Pad12)") (class "Default")
      (node (ref "U$1") (pin "12") (pinfunction "12_12") (pintype "bidirectional"))
    )
    (net (code "90") (name "unconnected-(U$1-Pad13)") (class "Default")
      (node (ref "U$1") (pin "13") (pinfunction "13_13") (pintype "bidirectional"))
    )
    (net (code "91") (name "unconnected-(U$1-Pad14)") (class "Default")
      (node (ref "U$1") (pin "14") (pinfunction "14_14") (pintype "bidirectional"))
    )
    (net (code "92") (name "unconnected-(U$1-Pad15)") (class "Default")
      (node (ref "U$1") (pin "15") (pinfunction "15_15") (pintype "bidirectional"))
    )
    (net (code "93") (name "unconnected-(U$1-Pad16)") (class "Default")
      (node (ref "U$1") (pin "16") (pinfunction "16_16") (pintype "bidirectional"))
    )
    (net (code "94") (name "unconnected-(U$1-Pad17)") (class "Default")
      (node (ref "U$1") (pin "17") (pinfunction "17_17") (pintype "bidirectional"))
    )
    (net (code "95") (name "unconnected-(U$1-Pad18)") (class "Default")
      (node (ref "U$1") (pin "18") (pinfunction "18_18") (pintype "bidirectional"))
    )
    (net (code "96") (name "unconnected-(U$1-Pad19)") (class "Default")
      (node (ref "U$1") (pin "19") (pinfunction "19_19") (pintype "bidirectional"))
    )
    (net (code "97") (name "unconnected-(U$1-Pad20)") (class "Default")
      (node (ref "U$1") (pin "20") (pinfunction "20_20") (pintype "bidirectional"))
    )
    (net (code "98") (name "unconnected-(U$1-Pad21)") (class "Default")
      (node (ref "U$1") (pin "21") (pinfunction "21_21") (pintype "bidirectional"))
    )
    (net (code "99") (name "unconnected-(U$1-Pad22)") (class "Default")
      (node (ref "U$1") (pin "22") (pinfunction "22_22") (pintype "bidirectional"))
    )
    (net (code "100") (name "unconnected-(U$1-Pad23)") (class "Default")
      (node (ref "U$1") (pin "23") (pinfunction "23_23") (pintype "bidirectional"))
    )
    (net (code "101") (name "unconnected-(U$1-Pad24)") (class "Default")
      (node (ref "U$1") (pin "24") (pinfunction "24_24") (pintype "bidirectional"))
    )
    (net (code "102") (name "unconnected-(U$1-Pad25)") (class "Default")
      (node (ref "U$1") (pin "25") (pinfunction "25_25") (pintype "bidirectional"))
    )
    (net (code "103") (name "unconnected-(U$1-Pad26)") (class "Default")
      (node (ref "U$1") (pin "26") (pinfunction "26_26") (pintype "bidirectional"))
    )
    (net (code "104") (name "unconnected-(U$1-Pad27)") (class "Default")
      (node (ref "U$1") (pin "27") (pinfunction "27_27") (pintype "bidirectional"))
    )
    (net (code "105") (name "unconnected-(U$1-Pad47)") (class "Default")
      (node (ref "U$1") (pin "47") (pinfunction "47_47") (pintype "bidirectional"))
    )
    (net (code "106") (name "unconnected-(U$1-Pad48)") (class "Default")
      (node (ref "U$1") (pin "48") (pinfunction "48_48") (pintype "bidirectional"))
    )
    (net (code "107") (name "unconnected-(U$1-Pad49)") (class "Default")
      (node (ref "U$1") (pin "49") (pinfunction "49_49") (pintype "bidirectional"))
    )
    (net (code "108") (name "unconnected-(U$1-Pad50)") (class "Default")
      (node (ref "U$1") (pin "50") (pinfunction "50_50") (pintype "bidirectional"))
    )
    (net (code "109") (name "unconnected-(U$1-Pad51)") (class "Default")
      (node (ref "U$1") (pin "51") (pinfunction "51_51") (pintype "bidirectional"))
    )
    (net (code "110") (name "unconnected-(U$1-Pad52)") (class "Default")
      (node (ref "U$1") (pin "52") (pinfunction "52_52") (pintype "output"))
    )
    (net (code "111") (name "unconnected-(U$1-Pad53)") (class "Default")
      (node (ref "U$1") (pin "53") (pinfunction "53_53") (pintype "input"))
    )
    (net (code "112") (name "unconnected-(U$1-Pad59)") (class "Default")
      (node (ref "U$1") (pin "59") (pinfunction "59_59") (pintype "bidirectional"))
    )
    (net (code "113") (name "unconnected-(U$1-Pad60)") (class "Default")
      (node (ref "U$1") (pin "60") (pinfunction "60_60") (pintype "bidirectional"))
    )
    (net (code "114") (name "unconnected-(U$2A-VRTC-PadP$25)") (class "Default")
      (node (ref "U$2") (pin "P$25") (pinfunction "VRTC_P$25") (pintype "passive"))
    )
    (net (code "115") (name "unconnected-(U$2B-ADC_IN1-PadP$26)") (class "Default")
      (node (ref "U$2") (pin "P$26") (pinfunction "ADC_IN1_P$26") (pintype "input"))
    )
    (net (code "116") (name "unconnected-(U$2B-ADC_IN2-PadP$27)") (class "Default")
      (node (ref "U$2") (pin "P$27") (pinfunction "ADC_IN2_P$27") (pintype "input"))
    )
    (net (code "117") (name "unconnected-(U$2B-ADC_IN3-PadP$28)") (class "Default")
      (node (ref "U$2") (pin "P$28") (pinfunction "ADC_IN3_P$28") (pintype "input"))
    )
    (net (code "118") (name "unconnected-(U$2B-DAC_OUT-PadP$20)") (class "Default")
      (node (ref "U$2") (pin "P$20") (pinfunction "DAC_OUT_P$20") (pintype "output"))
    )
    (net (code "119") (name "unconnected-(U$2C-EAR_HF+-PadP$57)") (class "Default")
      (node (ref "U$2") (pin "P$57") (pinfunction "EAR_HF+_P$57") (pintype "output"))
    )
    (net (code "120") (name "unconnected-(U$2C-EAR_MT+-PadP$55)") (class "Default")
      (node (ref "U$2") (pin "P$55") (pinfunction "EAR_MT+_P$55") (pintype "output"))
    )
    (net (code "121") (name "unconnected-(U$2C-EAR_MT--PadP$56)") (class "Default")
      (node (ref "U$2") (pin "P$56") (pinfunction "EAR_MT-_P$56") (pintype "output"))
    )
    (net (code "122") (name "unconnected-(U$2C-MIC_HF+-PadP$59)") (class "Default")
      (node (ref "U$2") (pin "P$59") (pinfunction "MIC_HF+_P$59") (pintype "input"))
    )
    (net (code "123") (name "unconnected-(U$2C-MIC_MT+-PadP$53)") (class "Default")
      (node (ref "U$2") (pin "P$53") (pinfunction "MIC_MT+_P$53") (pintype "input"))
    )
    (net (code "124") (name "unconnected-(U$2C-MIC_MT--PadP$54)") (class "Default")
      (node (ref "U$2") (pin "P$54") (pinfunction "MIC_MT-_P$54") (pintype "input"))
    )
    (net (code "125") (name "unconnected-(U$2D-GPIO1-PadP$21)") (class "Default")
      (node (ref "U$2") (pin "P$21") (pinfunction "GPIO1_P$21") (pintype "bidirectional"))
    )
    (net (code "126") (name "unconnected-(U$2D-GPIO2-PadP$22)") (class "Default")
      (node (ref "U$2") (pin "P$22") (pinfunction "GPIO2_P$22") (pintype "bidirectional"))
    )
    (net (code "127") (name "unconnected-(U$2D-GPIO3-PadP$23)") (class "Default")
      (node (ref "U$2") (pin "P$23") (pinfunction "GPIO3_P$23") (pintype "bidirectional"))
    )
    (net (code "128") (name "unconnected-(U$2D-GPIO4-PadP$24)") (class "Default")
      (node (ref "U$2") (pin "P$24") (pinfunction "GPIO4_P$24") (pintype "bidirectional"))
    )
    (net (code "129") (name "unconnected-(U$2D-GPIO5-PadP$35)") (class "Default")
      (node (ref "U$2") (pin "P$35") (pinfunction "GPIO5_P$35") (pintype "bidirectional"))
    )
    (net (code "130") (name "unconnected-(U$2D-GPIO7-PadP$31)") (class "Default")
      (node (ref "U$2") (pin "P$31") (pinfunction "GPIO7_P$31") (pintype "bidirectional"))
    )
    (net (code "131") (name "unconnected-(U$2D-OUT-PadP$32)") (class "Default")
      (node (ref "U$2") (pin "P$32") (pinfunction "OUT_P$32") (pintype "output"))
    )
    (net (code "132") (name "unconnected-(U$2F-CTS-PadP$40)") (class "Default")
      (node (ref "U$2") (pin "P$40") (pinfunction "CTS_P$40") (pintype "output"))
    )
    (net (code "133") (name "unconnected-(U$2F-DCD-PadP$38)") (class "Default")
      (node (ref "U$2") (pin "P$38") (pinfunction "DCD_P$38") (pintype "output"))
    )
    (net (code "134") (name "unconnected-(U$2F-RING-PadP$36)") (class "Default")
      (node (ref "U$2") (pin "P$36") (pinfunction "RING_P$36") (pintype "output"))
    )
  )
)
